# USB.net
KiCad netlist of a schematic drawn in Altium Designer
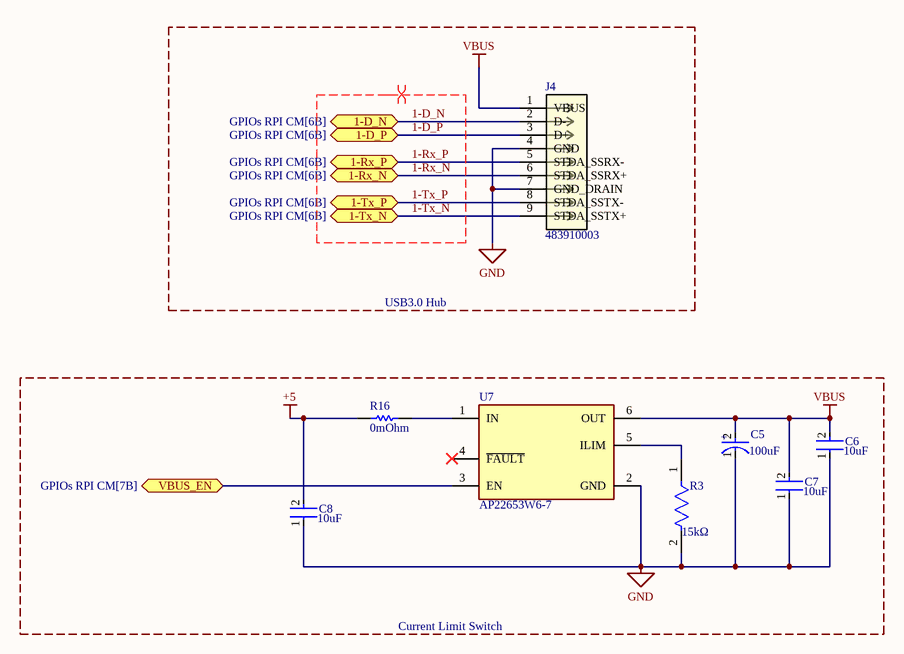
[diagram p0: USB.SchDoc]

(export (version "E")
  (design (tool "Eeschema 10.0.6"))
  (components
    (comp (ref "C5")
      (value "EEE-1AA101WR")
      (footprint "FP-SC-MFG")
      (description "CAP ALUM 100UF 20% 10V SMD")
      (fields (field (name "CAPACITANCE") "100uF") (field (name "TOLERANCE") "20%"))
      (libsource (lib "Altium Content Vault") (part "a00bbbee19879c290e62620ae7e47b1"))
    )
    (comp (ref "C6")
      (value "C1608X5R1A106K080AC")
      (footprint "FP-C1608-080-0_1-MFG")
      (description "Multilayer Ceramic Capacitors 10μF ±10% 10V X5R SMD 0603")
      (fields
        (field (name "VOLTAGE") "10V")
        (field (name "TOLERANCE") "10%")
        (field (name "CAPACITANCE") "10uF")
      )
      (libsource (lib "Altium Content Vault") (part "236180d848d6139a670b325ea6854c9"))
    )
    (comp (ref "C7")
      (value "C1608X5R1A106K080AC")
      (footprint "FP-C1608-080-0_1-MFG")
      (description "Multilayer Ceramic Capacitors 10μF ±10% 10V X5R SMD 0603")
      (fields
        (field (name "VOLTAGE") "10V")
        (field (name "TOLERANCE") "10%")
        (field (name "CAPACITANCE") "10uF")
      )
      (libsource (lib "Altium Content Vault") (part "236180d848d6139a670b325ea6854c9"))
    )
    (comp (ref "C8")
      (value "C1608X5R1A106K080AC")
      (footprint "FP-C1608-080-0_1-MFG")
      (description "Multilayer Ceramic Capacitors 10μF ±10% 10V X5R SMD 0603")
      (fields
        (field (name "VOLTAGE") "10V")
        (field (name "TOLERANCE") "10%")
        (field (name "CAPACITANCE") "10uF")
      )
      (libsource (lib "Altium Content Vault") (part "236180d848d6139a670b325ea6854c9"))
    )
    (comp (ref "J4")
      (value "483910003")
      (footprint "CONN_483910003_MOL")
      (description "No Description Available")
      (libsource (lib "483910003") (part "483910003"))
    )
    (comp (ref "R3")
      (value "ERJ-2RKF1502X")
      (footprint "FP-ERJ2R-MFG")
      (description "RES SMD 15K OHM 1% 1/10W 0402")
      (fields
        (field (name "TOLERANCE") "1%")
        (field (name "RESISTANCE") "15kΩ")
        (field (name "OCTOPART") "https://octopart.com/erj-2rkf1502x-panasonic-55404985")
      )
      (libsource (lib "Altium Content Vault") (part "1029c3af85768c4190bb7ad29bc67b5"))
    )
    (comp (ref "R16")
      (value "ERJ2GE0R00X")
      (footprint "RESC1005X40X25LL05T05")
      (description "Chip Resistor, 0 Ohm, 0.1 W, -55 to 155 degC, 0402 (1005 Metric), RoHS, Tape and Reel")
      (fields
        (field (name "MANUFACTURER") "Panasonic")
        (field (name "RESISTANCE") "0mOhm")
        (field (name "TOLERANCE") "5%")
      )
      (libsource (lib "Altium Content Vault") (part "RES-2"))
    )
    (comp (ref "U7")
      (value "AP22653W6-7")
      (footprint "FP-SOT26-MFG")
      (description "LOAD SWITCH,SOT26,T&R,3K")
      (libsource (lib "Altium Content Vault") (part "bad2b8b447a47ab10bab651f807ccff"))
    )
  )
  (nets
    (net (code "1") (name "+5") (class "Default")
      (node (ref "C8") (pin "2") (pinfunction "2_2") (pintype "passive"))
      (node (ref "R16") (pin "2") (pinfunction "2_2") (pintype "passive"))
    )
    (net (code "2") (name "/1-D_N") (class "Default")
      (node (ref "J4") (pin "2") (pinfunction "D-_2") (pintype "passive"))
    )
    (net (code "3") (name "/1-D_P") (class "Default")
      (node (ref "J4") (pin "3") (pinfunction "D+_3") (pintype "passive"))
    )
    (net (code "4") (name "/1-Rx_N") (class "Default")
      (node (ref "J4") (pin "6") (pinfunction "STDA_SSRX+_6") (pintype "passive"))
    )
    (net (code "5") (name "/1-Rx_P") (class "Default")
      (node (ref "J4") (pin "5") (pinfunction "STDA_SSRX-_5") (pintype "passive"))
    )
    (net (code "6") (name "/1-Tx_N") (class "Default")
      (node (ref "J4") (pin "9") (pinfunction "STDA_SSTX+_9") (pintype "passive"))
    )
    (net (code "7") (name "/1-Tx_P") (class "Default")
      (node (ref "J4") (pin "8") (pinfunction "STDA_SSTX-_8") (pintype "passive"))
    )
    (net (code "8") (name "/VBUS_EN") (class "Default")
      (node (ref "U7") (pin "3") (pinfunction "EN_3") (pintype "passive"))
    )
    (net (code "9") (name "GND") (class "Default")
      (node (ref "C5") (pin "1") (pinfunction "C_1") (pintype "passive"))
      (node (ref "C6") (pin "1") (pinfunction "1_1") (pintype "passive"))
      (node (ref "C7") (pin "1") (pinfunction "1_1") (pintype "passive"))
      (node (ref "C8") (pin "1") (pinfunction "1_1") (pintype "passive"))
      (node (ref "J4") (pin "4") (pinfunction "GND_4") (pintype "passive"))
      (node (ref "J4") (pin "7") (pinfunction "GND_DRAIN_7") (pintype "passive"))
      (node (ref "R3") (pin "2") (pinfunction "2_2") (pintype "passive"))
      (node (ref "U7") (pin "2") (pinfunction "GND_2") (pintype "power_in"))
    )
    (net (code "10") (name "Net-(U7-ILIM)") (class "Default")
      (node (ref "R3") (pin "1") (pinfunction "1_1") (pintype "passive"))
      (node (ref "U7") (pin "5") (pinfunction "ILIM_5") (pintype "passive"))
    )
    (net (code "11") (name "Net-(U7-IN)") (class "Default")
      (node (ref "R16") (pin "1") (pinfunction "1_1") (pintype "passive"))
      (node (ref "U7") (pin "1") (pinfunction "IN_1") (pintype "power_in"))
    )
    (net (code "12") (name "VBUS") (class "Default")
      (node (ref "C5") (pin "2") (pinfunction "A_2") (pintype "passive"))
      (node (ref "C6") (pin "2") (pinfunction "2_2") (pintype "passive"))
      (node (ref "C7") (pin "2") (pinfunction "2_2") (pintype "passive"))
      (node (ref "J4") (pin "1") (pinfunction "VBUS_1") (pintype "passive"))
      (node (ref "U7") (pin "6") (pinfunction "OUT_6") (pintype "passive"))
    )
    (net (code "13") (name "unconnected-(U7-~{FAULT}-Pad4)") (class "Default")
      (node (ref "U7") (pin "4") (pinfunction "~{FAULT}_4") (pintype "open_collector+no_connect"))
    )
  )
)
